# CH340G.net
KiCad netlist of a schematic drawn in Altium Designer
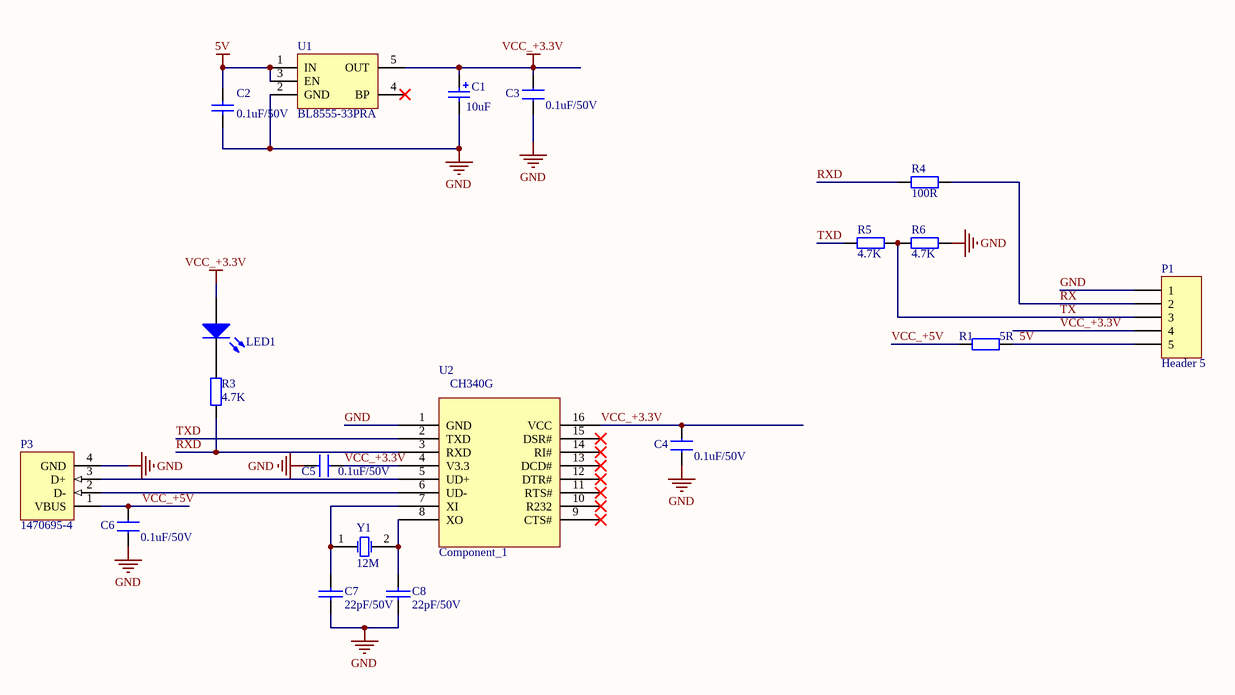
[diagram p0: CH340G.SchDoc]

(export (version "E")
  (design (tool "Eeschema 10.0.6"))
  (components
    (comp (ref "C1")
      (value "10uF")
      (footprint "1206-C")
      (description "Polarized Capacitor (Radial)")
      (fields (field (name "PUBLISHER") "Altium Limited"))
      (libsource (lib "Calf") (part "Cap Pol"))
    )
    (comp (ref "C2")
      (value "0.1uF/50V")
      (footprint "0603C")
      (description "Capacitor")
      (fields (field (name "PUBLISHER") "Altium Limited"))
      (libsource (lib "Calf") (part "Cap"))
    )
    (comp (ref "C3") (value "0.1uF/50V") (footprint "0603C") (libsource (lib "0603C") (part "CAP")))
    (comp (ref "C4") (value "0.1uF/50V") (footprint "0603C") (libsource (lib "0603C") (part "CAP")))
    (comp (ref "C5") (value "0.1uF/50V") (footprint "0603C") (libsource (lib "0603C") (part "CAP")))
    (comp (ref "C6") (value "0.1uF/50V") (footprint "0603C") (libsource (lib "0603C") (part "CAP")))
    (comp (ref "C7") (value "22pF/50V") (footprint "0603C") (libsource (lib "*") (part "0603C")))
    (comp (ref "C8") (value "22pF/50V") (footprint "0603C") (libsource (lib "*") (part "0603C")))
    (comp (ref "LED1")
      (value "LED")
      (footprint "LED-0603")
      (description "BLUE LED")
      (fields (field (name "PUBLISHER") "Altium Limited"))
      (libsource (lib "Schlib") (part "LED3"))
    )
    (comp (ref "P1")
      (value "Header 5")
      (footprint "HDR1X5")
      (description "Header, 5-Pin")
      (fields (field (name "PUBLISHER") "Altium Limited"))
      (libsource (lib "Miscellaneous Connectors") (part "Header 5"))
    )
    (comp (ref "P3")
      (value "1470695-4")
      (footprint "USB1019")
      (description "USB 1.1, Right Angle, SMT, A Type, Plug, 4 Position, Black")
      (fields (field (name "PUBLISHER") "Altium Limited"))
      (libsource (lib "*") (part "1470695-4"))
    )
    (comp (ref "R1") (value "5R") (footprint "1206R") (libsource (lib "*") (part "0603R")))
    (comp (ref "R3") (value "4.7K") (footprint "0603R") (libsource (lib "") (part "0603R_1")))
    (comp (ref "R4") (value "100R") (footprint "0603R") (libsource (lib "*") (part "0603R")))
    (comp (ref "R5") (value "4.7K") (footprint "0603R") (libsource (lib "*") (part "0603R")))
    (comp (ref "R6") (value "4.7K") (footprint "0603R") (libsource (lib "") (part "0603R_2")))
    (comp (ref "U1") (value "BL8555-33PRA") (footprint "SOT23-5") (libsource (lib "Calf") (part "SGM2019")))
    (comp (ref "U2")
      (value "Component_1")
      (footprint "SO-16")
      (libsource (lib "CH340G") (part "Component_1"))
    )
    (comp (ref "Y1")
      (value "12M")
      (footprint "XTAL")
      (description "Crystal Oscillator")
      (fields (field (name "PUBLISHER") "Altium Limited"))
      (libsource (lib "*") (part "XTAL"))
    )
  )
  (nets
    (net (code "1") (name "/RX") (class "Default")
      (node (ref "P1") (pin "2") (pinfunction "2_2") (pintype "passive"))
      (node (ref "R4") (pin "2") (pinfunction "2_2") (pintype "passive"))
    )
    (net (code "2") (name "/RXD") (class "Default")
      (node (ref "R3") (pin "2") (pinfunction "2_2") (pintype "passive"))
      (node (ref "R4") (pin "1") (pinfunction "1_1") (pintype "passive"))
      (node (ref "U2") (pin "3") (pinfunction "RXD_3") (pintype "passive"))
    )
    (net (code "3") (name "/TX") (class "Default")
      (node (ref "P1") (pin "3") (pinfunction "3_3") (pintype "passive"))
      (node (ref "R5") (pin "2") (pinfunction "2_2") (pintype "passive"))
      (node (ref "R6") (pin "2") (pinfunction "2_2") (pintype "passive"))
    )
    (net (code "4") (name "/TXD") (class "Default")
      (node (ref "R5") (pin "1") (pinfunction "1_1") (pintype "passive"))
      (node (ref "U2") (pin "2") (pinfunction "TXD_2") (pintype "passive"))
    )
    (net (code "5") (name "/VCC_+5V") (class "Default")
      (node (ref "C6") (pin "1") (pinfunction "1_1") (pintype "passive"))
      (node (ref "P3") (pin "1") (pinfunction "VBUS_1") (pintype "power_in"))
      (node (ref "R1") (pin "1") (pinfunction "1_1") (pintype "passive"))
    )
    (net (code "6") (name "5V") (class "Default")
      (node (ref "C2") (pin "2") (pinfunction "2_2") (pintype "passive"))
      (node (ref "P1") (pin "5") (pinfunction "5_5") (pintype "passive"))
      (node (ref "R1") (pin "2") (pinfunction "2_2") (pintype "passive"))
      (node (ref "U1") (pin "1") (pinfunction "IN_1") (pintype "passive"))
      (node (ref "U1") (pin "3") (pinfunction "EN_3") (pintype "passive"))
    )
    (net (code "7") (name "GND") (class "Default")
      (node (ref "C1") (pin "2") (pinfunction "2_2") (pintype "passive"))
      (node (ref "C2") (pin "1") (pinfunction "1_1") (pintype "passive"))
      (node (ref "C3") (pin "2") (pinfunction "2_2") (pintype "passive"))
      (node (ref "C4") (pin "2") (pinfunction "2_2") (pintype "passive"))
      (node (ref "C5") (pin "1") (pinfunction "1_1") (pintype "passive"))
      (node (ref "C6") (pin "2") (pinfunction "2_2") (pintype "passive"))
      (node (ref "C7") (pin "1") (pintype "passive"))
      (node (ref "C8") (pin "1") (pintype "passive"))
      (node (ref "P1") (pin "1") (pinfunction "1_1") (pintype "passive"))
      (node (ref "P3") (pin "4") (pinfunction "GND_4") (pintype "power_in"))
      (node (ref "R6") (pin "1") (pinfunction "1_1") (pintype "passive"))
      (node (ref "U1") (pin "2") (pinfunction "GND_2") (pintype "passive"))
      (node (ref "U2") (pin "1") (pinfunction "GND_1") (pintype "passive"))
    )
    (net (code "8") (name "Net-(LED1-K)") (class "Default")
      (node (ref "LED1") (pin "2") (pinfunction "K_2") (pintype "passive"))
      (node (ref "R3") (pin "1") (pinfunction "1_1") (pintype "passive"))
    )
    (net (code "9") (name "Net-(P3-D+)") (class "Default")
      (node (ref "P3") (pin "3") (pinfunction "D+_3") (pintype "input"))
      (node (ref "U2") (pin "5") (pinfunction "UD+_5") (pintype "passive"))
    )
    (net (code "10") (name "Net-(P3-D-)") (class "Default")
      (node (ref "P3") (pin "2") (pinfunction "D-_2") (pintype "input"))
      (node (ref "U2") (pin "6") (pinfunction "UD-_6") (pintype "passive"))
    )
    (net (code "11") (name "Net-(U2-XI)") (class "Default")
      (node (ref "C7") (pin "2") (pintype "passive"))
      (node (ref "U2") (pin "7") (pinfunction "XI_7") (pintype "passive"))
      (node (ref "Y1") (pin "1") (pinfunction "OSC1_1") (pintype "passive"))
    )
    (net (code "12") (name "Net-(U2-XO)") (class "Default")
      (node (ref "C8") (pin "2") (pintype "passive"))
      (node (ref "U2") (pin "8") (pinfunction "XO_8") (pintype "passive"))
      (node (ref "Y1") (pin "2") (pinfunction "OSC2_2") (pintype "passive"))
    )
    (net (code "13") (name "VCC_+3.3V") (class "Default")
      (node (ref "C1") (pin "1") (pinfunction "1_1") (pintype "passive"))
      (node (ref "C3") (pin "1") (pinfunction "1_1") (pintype "passive"))
      (node (ref "C4") (pin "1") (pinfunction "1_1") (pintype "passive"))
      (node (ref "C5") (pin "2") (pinfunction "2_2") (pintype "passive"))
      (node (ref "LED1") (pin "1") (pinfunction "A_1") (pintype "passive"))
      (node (ref "P1") (pin "4") (pinfunction "4_4") (pintype "passive"))
      (node (ref "U1") (pin "5") (pinfunction "OUT_5") (pintype "passive"))
      (node (ref "U2") (pin "16") (pinfunction "VCC_16") (pintype "passive"))
      (node (ref "U2") (pin "4") (pinfunction "V3.3_4") (pintype "passive"))
    )
    (net (code "14") (name "unconnected-(U1-BP-Pad4)") (class "Default")
      (node (ref "U1") (pin "4") (pinfunction "BP_4") (pintype "passive+no_connect"))
    )
    (net (code "15") (name "unconnected-(U2-CTS#-Pad9)") (class "Default")
      (node (ref "U2") (pin "9") (pinfunction "CTS#_9") (pintype "passive+no_connect"))
    )
    (net (code "16") (name "unconnected-(U2-DCD#-Pad13)") (class "Default")
      (node (ref "U2") (pin "13") (pinfunction "DCD#_13") (pintype "passive+no_connect"))
    )
    (net (code "17") (name "unconnected-(U2-DSR#-Pad15)") (class "Default")
      (node (ref "U2") (pin "15") (pinfunction "DSR#_15") (pintype "passive+no_connect"))
    )
    (net (code "18") (name "unconnected-(U2-DTR#-Pad12)") (class "Default")
      (node (ref "U2") (pin "12") (pinfunction "DTR#_12") (pintype "passive+no_connect"))
    )
    (net (code "19") (name "unconnected-(U2-R232-Pad10)") (class "Default")
      (node (ref "U2") (pin "10") (pinfunction "R232_10") (pintype "passive+no_connect"))
    )
    (net (code "20") (name "unconnected-(U2-RI#-Pad14)") (class "Default")
      (node (ref "U2") (pin "14") (pinfunction "RI#_14") (pintype "passive+no_connect"))
    )
    (net (code "21") (name "unconnected-(U2-RTS#-Pad11)") (class "Default")
      (node (ref "U2") (pin "11") (pinfunction "RTS#_11") (pintype "passive+no_connect"))
    )
  )
)
